# Ethernet_PHY.net
KiCad netlist of a schematic drawn in Altium Designer
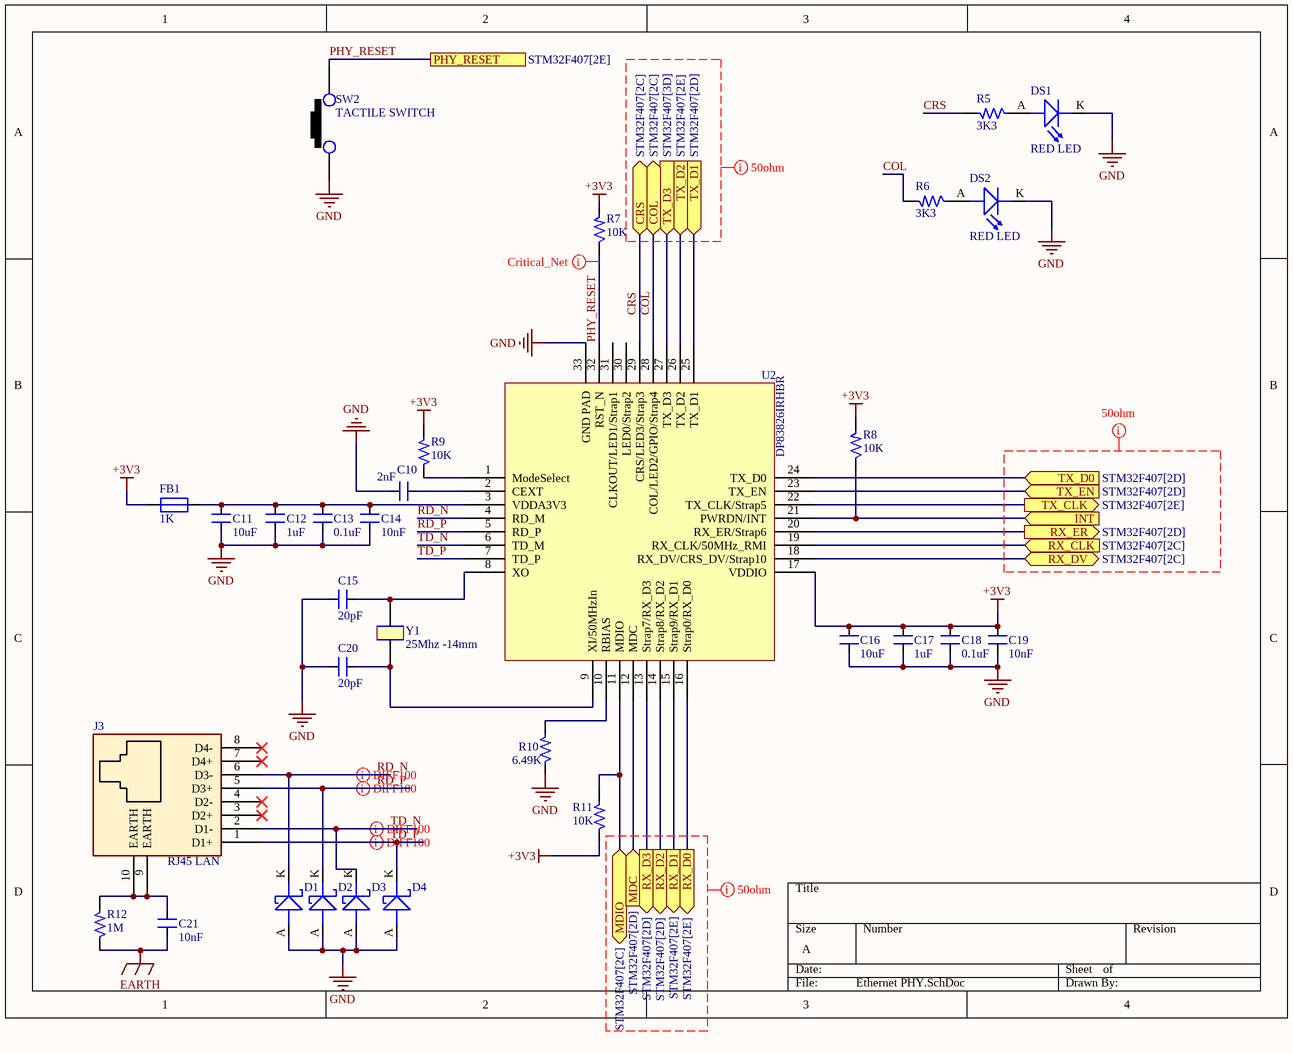
[diagram p0: Ethernet PHY.SchDoc]

(export (version "E")
  (design (tool "Eeschema 10.0.6"))
  (components
    (comp (ref "C10")
      (value "2nF")
      (footprint "CAP_0805")
      (description "2000pF ±10% 50V Ceramic Capacitor X7R 0805 (2012 Metric)")
      (fields
        (field (name "MANUFACTURER") "Samsung Electro-Mechanics")
        (field (name "MANUFACTURER PART NUMBER") "CL21B202KBANNNC")
      )
      (libsource (lib "ESTEEMPCBLIB") (part "CAP_2nF-50V-10%-0805"))
    )
    (comp (ref "C11")
      (value "10uF")
      (footprint "CAP_1206")
      (description "10µF ±10% 50V Ceramic Capacitor X7R 1206 (3216 Metric)")
      (fields
        (field (name "MANUFACTURER") "KEMET")
        (field (name "MANUFACTURER PART NUMBER") "CL31B106KBHNNNE")
      )
      (libsource (lib "ESTEEMPCBLIB") (part "CAP_10uF-50V-10%-1206"))
    )
    (comp (ref "C12")
      (value "1uF")
      (footprint "CAP_0805")
      (description "1µF ±5% 50V Ceramic Capacitor X7R 0805 (2012 Metric)")
      (fields
        (field (name "MANUFACTURER") "Samsung")
        (field (name "MANUFACTURER PART NUMBER") "CC0805JKX7R9BB105")
      )
      (libsource (lib "ESTEEMPCBLIB") (part "CAP_1uF-50V-5%-0805"))
    )
    (comp (ref "C13")
      (value "0.1uF")
      (footprint "CAP_0805")
      (description "0.1µF ±10% 50V Ceramic Capacitor X7R 0805 (2012 Metric)")
      (fields
        (field (name "MANUFACTURER") "Samsung")
        (field (name "MANUFACTURER PART NUMBER") "CL21B104KBCNNNC")
      )
      (libsource (lib "ESTEEMPCBLIB") (part "CAP_0.1uF-50V-10%-0805"))
    )
    (comp (ref "C14")
      (value "10nF")
      (footprint "CAP_0805")
      (description "10000pF ±10% 50V Ceramic Capacitor X7R 0805 (2012 Metric)")
      (fields
        (field (name "MANUFACTURER") "Samsung")
        (field (name "MANUFACTURER PART NUMBER") "C0805C103K5RECAUTO")
      )
      (libsource (lib "ESTEEMPCBLIB") (part "CAP_10nF-50V-10%-0805"))
    )
    (comp (ref "C15")
      (value "20pF")
      (footprint "CAP_0805")
      (description "±10% 50V Ceramic Capacitor C0G, NP0 0805 (2012 Metric)")
      (fields
        (field (name "MANUFACTURER") "AVX Corporation")
        (field (name "MANUFACTURER PART NUMBER") "08055A200KAT2A")
      )
      (libsource (lib "ESTEEMPCBLIB") (part "CAP_20pF-50V-10%-0805"))
    )
    (comp (ref "C16")
      (value "10uF")
      (footprint "CAP_1206")
      (description "10µF ±10% 50V Ceramic Capacitor X7R 1206 (3216 Metric)")
      (fields
        (field (name "MANUFACTURER") "KEMET")
        (field (name "MANUFACTURER PART NUMBER") "CL31B106KBHNNNE")
      )
      (libsource (lib "ESTEEMPCBLIB") (part "CAP_10uF-50V-10%-1206"))
    )
    (comp (ref "C17")
      (value "1uF")
      (footprint "CAP_0805")
      (description "1µF ±5% 50V Ceramic Capacitor X7R 0805 (2012 Metric)")
      (fields
        (field (name "MANUFACTURER") "Samsung")
        (field (name "MANUFACTURER PART NUMBER") "CC0805JKX7R9BB105")
      )
      (libsource (lib "ESTEEMPCBLIB") (part "CAP_1uF-50V-5%-0805"))
    )
    (comp (ref "C18")
      (value "0.1uF")
      (footprint "CAP_0805")
      (description "0.1µF ±10% 50V Ceramic Capacitor X7R 0805 (2012 Metric)")
      (fields
        (field (name "MANUFACTURER") "Samsung")
        (field (name "MANUFACTURER PART NUMBER") "CL21B104KBCNNNC")
      )
      (libsource (lib "ESTEEMPCBLIB") (part "CAP_0.1uF-50V-10%-0805"))
    )
    (comp (ref "C19")
      (value "10nF")
      (footprint "CAP_0805")
      (description "10000pF ±10% 50V Ceramic Capacitor X7R 0805 (2012 Metric)")
      (fields
        (field (name "MANUFACTURER") "Samsung")
        (field (name "MANUFACTURER PART NUMBER") "C0805C103K5RECAUTO")
      )
      (libsource (lib "ESTEEMPCBLIB") (part "CAP_10nF-50V-10%-0805"))
    )
    (comp (ref "C20")
      (value "20pF")
      (footprint "CAP_0805")
      (description "±10% 50V Ceramic Capacitor C0G, NP0 0805 (2012 Metric)")
      (fields
        (field (name "MANUFACTURER") "AVX Corporation")
        (field (name "MANUFACTURER PART NUMBER") "08055A200KAT2A")
      )
      (libsource (lib "ESTEEMPCBLIB") (part "CAP_20pF-50V-10%-0805"))
    )
    (comp (ref "C21")
      (value "10nF")
      (footprint "CAP_P196_102X287_H332_RAD_TH")
      (description "10000pF ±10% 1000V (1kV) Ceramic Capacitor X7R Radial")
      (fields
        (field (name "MANUFACTURER") "Yageo")
        (field (name "MANUFACTURER PART NUMBER") "RDER73A103K2K1H03B")
      )
      (libsource (lib "ESTEEMPCBLIB") (part "CAP_10nF-1KV-10%-RAD-TH"))
    )
    (comp (ref "D1")
      (value "ESD3V3D9-TP")
      (footprint "DIO_SOD-923")
      (description "TVS DIODE 3.3V 8.8V SOD923")
      (fields (field (name "MANUFACTURER") "Micro Commercial Co"))
      (libsource (lib "ESTEEMPCBLIB") (part "DIO-T_3.3V-8.8V-10A-SOD923"))
    )
    (comp (ref "D2")
      (value "ESD3V3D9-TP")
      (footprint "DIO_SOD-923")
      (description "TVS DIODE 3.3V 8.8V SOD923")
      (fields (field (name "MANUFACTURER") "Micro Commercial Co"))
      (libsource (lib "ESTEEMPCBLIB") (part "DIO-T_3.3V-8.8V-10A-SOD923"))
    )
    (comp (ref "D3")
      (value "ESD3V3D9-TP")
      (footprint "DIO_SOD-923")
      (description "TVS DIODE 3.3V 8.8V SOD923")
      (fields (field (name "MANUFACTURER") "Micro Commercial Co"))
      (libsource (lib "ESTEEMPCBLIB") (part "DIO-T_3.3V-8.8V-10A-SOD923"))
    )
    (comp (ref "D4")
      (value "ESD3V3D9-TP")
      (footprint "DIO_SOD-923")
      (description "TVS DIODE 3.3V 8.8V SOD923")
      (fields (field (name "MANUFACTURER") "Micro Commercial Co"))
      (libsource (lib "ESTEEMPCBLIB") (part "DIO-T_3.3V-8.8V-10A-SOD923"))
    )
    (comp (ref "DS1")
      (value "RED LED")
      (footprint "LED_0805")
      (description "Red 631nm LED Indication - Discrete 2V 0805 (2012 Metric)")
      (fields
        (field (name "MANUFACTURER") "Vishay Lite-On")
        (field (name "MANUFACTURER PART NUMBER") "LTST-C171KRKT")
      )
      (libsource (lib "ESTEEMPCBLIB") (part "LED_RED-2V-20mA-0805"))
    )
    (comp (ref "DS2")
      (value "RED LED")
      (footprint "LED_0805")
      (description "Red 631nm LED Indication - Discrete 2V 0805 (2012 Metric)")
      (fields
        (field (name "MANUFACTURER") "Vishay Lite-On")
        (field (name "MANUFACTURER PART NUMBER") "LTST-C171KRKT")
      )
      (libsource (lib "ESTEEMPCBLIB") (part "LED_RED-2V-20mA-0805"))
    )
    (comp (ref "FB1")
      (value "1K")
      (footprint "IND_0805")
      (description "1 kOhms @ 100MHz 1 Power Line Ferrite Bead 0805 (2012 Metric) 1.6A")
      (fields
        (field (name "MANUFACTURER") "Laird")
        (field (name "MANUFACTURER PART NUMBER") "BLM21SP102SH1D")
      )
      (libsource (lib "ESTEEMPCBLIB") (part "FB_1K-100MHZ-1.6A-0805"))
    )
    (comp (ref "J3")
      (value "RJ45 LAN")
      (footprint "CON10_P106_RJ45_TH_ST")
      (description "8 Pins, 2 Row 2.54mm Pitch, right angle Connector, male")
      (fields
        (field (name "MANUFACTURER") "Assmann")
        (field (name "MANUFACTURER PART NUMBER") "A-2004-2-4-LPS-N-R")
      )
      (libsource (lib "ESTEEMPCBLIB") (part "CON-SKT-RJ_8C8P-RA-TH"))
    )
    (comp (ref "R5")
      (value "3K3")
      (footprint "RES_0603")
      (description "3.3 kOhms ±1% 0.1W, 1/10W Chip Resistor 0603 (1608 Metric) Automotive AEC-Q200 Thick Film")
      (fields (field (name "MANUFACTURER") "Wilson") (field (name "MANUFACTURER PART NUMBER") "WR06X3301FTL"))
      (libsource (lib "ESTEEMPCBLIB") (part "RES_3.3K-0.1W-1%-0603"))
    )
    (comp (ref "R6")
      (value "3K3")
      (footprint "RES_0603")
      (description "3.3 kOhms ±1% 0.1W, 1/10W Chip Resistor 0603 (1608 Metric) Automotive AEC-Q200 Thick Film")
      (fields (field (name "MANUFACTURER") "Wilson") (field (name "MANUFACTURER PART NUMBER") "WR06X3301FTL"))
      (libsource (lib "ESTEEMPCBLIB") (part "RES_3.3K-0.1W-1%-0603"))
    )
    (comp (ref "R7")
      (value "10K")
      (footprint "RES_0603")
      (description "10 kOhms ±1% 0.1W, 1/10W Chip Resistor 0603 (1608 Metric) Automotive AEC-Q200 Thick Film")
      (fields (field (name "MANUFACTURER") "Walsin") (field (name "MANUFACTURER PART NUMBER") "WR06X1002FTL"))
      (libsource (lib "ESTEEMPCBLIB") (part "RES_10K-0.1W-1%-0603"))
    )
    (comp (ref "R8")
      (value "10K")
      (footprint "RES_0603")
      (description "10 kOhms ±1% 0.1W, 1/10W Chip Resistor 0603 (1608 Metric) Automotive AEC-Q200 Thick Film")
      (fields (field (name "MANUFACTURER") "Walsin") (field (name "MANUFACTURER PART NUMBER") "WR06X1002FTL"))
      (libsource (lib "ESTEEMPCBLIB") (part "RES_10K-0.1W-1%-0603"))
    )
    (comp (ref "R9")
      (value "10K")
      (footprint "RES_0603")
      (description "10 kOhms ±1% 0.1W, 1/10W Chip Resistor 0603 (1608 Metric) Automotive AEC-Q200 Thick Film")
      (fields (field (name "MANUFACTURER") "Walsin") (field (name "MANUFACTURER PART NUMBER") "WR06X1002FTL"))
      (libsource (lib "ESTEEMPCBLIB") (part "RES_10K-0.1W-1%-0603"))
    )
    (comp (ref "R10")
      (value "6.49K")
      (footprint "RES_0805")
      (description "6.49 kOhms ±1% 0.125W, 1/8W Chip Resistor 0805 (2012 Metric) Moisture Resistant Thick Film")
      (fields
        (field (name "MANUFACTURER") "Stackpole Electronics")
        (field (name "MANUFACTURER PART NUMBER") "RC0805FR-076K49L")
      )
      (libsource (lib "ESTEEMPCBLIB") (part "RES_6.49K-0.125W-1%-0805"))
    )
    (comp (ref "R11")
      (value "10K")
      (footprint "RES_0603")
      (description "10 kOhms ±1% 0.1W, 1/10W Chip Resistor 0603 (1608 Metric) Automotive AEC-Q200 Thick Film")
      (fields (field (name "MANUFACTURER") "Walsin") (field (name "MANUFACTURER PART NUMBER") "WR06X1002FTL"))
      (libsource (lib "ESTEEMPCBLIB") (part "RES_10K-0.1W-1%-0603"))
    )
    (comp (ref "R12")
      (value "1M")
      (footprint "RES_1206")
      (fields (field (name "MANUFACTURER") "Walsin") (field (name "MANUFACTURER PART NUMBER") "WR12X1004FTL"))
      (libsource (lib "ESTEEMPCBLIB") (part "RES_1M-0.25W-1%-1206"))
    )
    (comp (ref "SW2")
      (value "TACTILE SWITCH")
      (footprint "SW_342_SMD")
      (description "Tactile Switch SPST-NO Top Actuated Surface Mount")
      (fields
        (field (name "MANUFACTURER") "ITT C&K")
        (field (name "MANUFACTURER PART NUMBER") "RS-282G05A3-SMRT")
      )
      (libsource (lib "ESTEEMPCBLIB") (part "SW1_RS-282G05A3-SMRT-SMD"))
    )
    (comp (ref "U2")
      (value "DP83826IRHBR")
      (footprint "VQFN32_19_218_23X9_SMD")
      (fields (field (name "MANUFACTURER") "Texas Instruments"))
      (libsource (lib "ESTEEMPCBLIB") (part "IC_DP83826IRHBR"))
    )
    (comp (ref "Y1")
      (value "25Mhz -14mm")
      (footprint "XTAL_314_240X47_SMD")
      (description "25MHz ±30ppm Crystal 20pF 30 Ohms HC-49/US")
      (fields
        (field (name "MANUFACTURER") "Abracon")
        (field (name "MANUFACTURER PART NUMBER") "FOXSDLF/250F-20")
      )
      (libsource (lib "ESTEEMPCBLIB") (part "XTAL_25Mhz-FOXSDLF/250F-20"))
    )
  )
  (nets
    (net (code "1") (name "+3V3") (class "Default")
      (node (ref "C16") (pin "1") (pinfunction "1_1") (pintype "passive"))
      (node (ref "C17") (pin "2") (pinfunction "2_2") (pintype "passive"))
      (node (ref "C18") (pin "2") (pinfunction "2_2") (pintype "passive"))
      (node (ref "C19") (pin "1") (pinfunction "1_1") (pintype "passive"))
      (node (ref "FB1") (pin "1") (pinfunction "1_1") (pintype "passive"))
      (node (ref "R11") (pin "1") (pinfunction "1_1") (pintype "passive"))
      (node (ref "R7") (pin "2") (pinfunction "2_2") (pintype "passive"))
      (node (ref "R8") (pin "2") (pinfunction "2_2") (pintype "passive"))
      (node (ref "R9") (pin "2") (pinfunction "2_2") (pintype "passive"))
      (node (ref "U2") (pin "17") (pinfunction "VDDIO_17") (pintype "passive"))
    )
    (net (code "2") (name "/COL") (class "Default")
      (node (ref "R6") (pin "2") (pinfunction "2_2") (pintype "passive"))
      (node (ref "U2") (pin "28") (pinfunction "COL/LED2/GPIO/Strap4_28") (pintype "passive"))
    )
    (net (code "3") (name "/CRS") (class "Default")
      (node (ref "R5") (pin "2") (pinfunction "2_2") (pintype "passive"))
      (node (ref "U2") (pin "29") (pinfunction "CRS/LED3/Strap3_29") (pintype "passive"))
    )
    (net (code "4") (name "/INT") (class "Default")
      (node (ref "R8") (pin "1") (pinfunction "1_1") (pintype "passive"))
      (node (ref "U2") (pin "21") (pinfunction "PWRDN/INT_21") (pintype "passive"))
    )
    (net (code "5") (name "/MDC") (class "Default")
      (node (ref "U2") (pin "12") (pinfunction "MDC_12") (pintype "passive"))
    )
    (net (code "6") (name "/MDIO") (class "Default")
      (node (ref "R11") (pin "2") (pinfunction "2_2") (pintype "passive"))
      (node (ref "U2") (pin "11") (pinfunction "MDIO_11") (pintype "passive"))
    )
    (net (code "7") (name "/PHY_RESET") (class "Default")
      (node (ref "R7") (pin "1") (pinfunction "1_1") (pintype "passive"))
      (node (ref "SW2") (pin "2") (pinfunction "2_2") (pintype "passive"))
      (node (ref "U2") (pin "32") (pinfunction "RST_N_32") (pintype "passive"))
    )
    (net (code "8") (name "/RD_N") (class "Default")
      (node (ref "D1") (pin "K") (pinfunction "K_K") (pintype "passive"))
      (node (ref "J3") (pin "6") (pinfunction "D3-_6") (pintype "passive"))
      (node (ref "U2") (pin "4") (pinfunction "RD_M_4") (pintype "passive"))
    )
    (net (code "9") (name "/RD_P") (class "Default")
      (node (ref "D2") (pin "K") (pinfunction "K_K") (pintype "passive"))
      (node (ref "J3") (pin "5") (pinfunction "D3+_5") (pintype "passive"))
      (node (ref "U2") (pin "5") (pinfunction "RD_P_5") (pintype "passive"))
    )
    (net (code "10") (name "/RX_CLK") (class "Default")
      (node (ref "U2") (pin "19") (pinfunction "RX_CLK/50MHz_RMI_19") (pintype "passive"))
    )
    (net (code "11") (name "/RX_D0") (class "Default")
      (node (ref "U2") (pin "16") (pinfunction "Strap0/RX_D0_16") (pintype "passive"))
    )
    (net (code "12") (name "/RX_D1") (class "Default")
      (node (ref "U2") (pin "15") (pinfunction "Strap9/RX_D1_15") (pintype "passive"))
    )
    (net (code "13") (name "/RX_D2") (class "Default")
      (node (ref "U2") (pin "14") (pinfunction "Strap8/RX_D2_14") (pintype "passive"))
    )
    (net (code "14") (name "/RX_D3") (class "Default")
      (node (ref "U2") (pin "13") (pinfunction "Strap7/RX_D3_13") (pintype "passive"))
    )
    (net (code "15") (name "/RX_DV") (class "Default")
      (node (ref "U2") (pin "18") (pinfunction "RX_DV/CRS_DV/Strap10_18") (pintype "passive"))
    )
    (net (code "16") (name "/RX_ER") (class "Default")
      (node (ref "U2") (pin "20") (pinfunction "RX_ER/Strap6_20") (pintype "passive"))
    )
    (net (code "17") (name "/TD_N") (class "Default")
      (node (ref "D3") (pin "K") (pinfunction "K_K") (pintype "passive"))
      (node (ref "J3") (pin "2") (pinfunction "D1-_2") (pintype "passive"))
      (node (ref "U2") (pin "6") (pinfunction "TD_M_6") (pintype "passive"))
    )
    (net (code "18") (name "/TD_P") (class "Default")
      (node (ref "D4") (pin "K") (pinfunction "K_K") (pintype "passive"))
      (node (ref "J3") (pin "1") (pinfunction "D1+_1") (pintype "passive"))
      (node (ref "U2") (pin "7") (pinfunction "TD_P_7") (pintype "passive"))
    )
    (net (code "19") (name "/TX_CLK") (class "Default")
      (node (ref "U2") (pin "22") (pinfunction "TX_CLK/Strap5_22") (pintype "passive"))
    )
    (net (code "20") (name "/TX_D0") (class "Default")
      (node (ref "U2") (pin "24") (pinfunction "TX_D0_24") (pintype "passive"))
    )
    (net (code "21") (name "/TX_D1") (class "Default")
      (node (ref "U2") (pin "25") (pinfunction "TX_D1_25") (pintype "passive"))
    )
    (net (code "22") (name "/TX_D2") (class "Default")
      (node (ref "U2") (pin "26") (pinfunction "TX_D2_26") (pintype "passive"))
    )
    (net (code "23") (name "/TX_D3") (class "Default")
      (node (ref "U2") (pin "27") (pinfunction "TX_D3_27") (pintype "passive"))
    )
    (net (code "24") (name "/TX_EN") (class "Default")
      (node (ref "U2") (pin "23") (pinfunction "TX_EN_23") (pintype "passive"))
    )
    (net (code "25") (name "EARTH") (class "Default")
      (node (ref "C21") (pin "2") (pinfunction "2_2") (pintype "passive"))
      (node (ref "R12") (pin "1") (pinfunction "1_1") (pintype "passive"))
    )
    (net (code "26") (name "GND") (class "Default")
      (node (ref "C10") (pin "1") (pinfunction "1_1") (pintype "passive"))
      (node (ref "C11") (pin "2") (pinfunction "2_2") (pintype "passive"))
      (node (ref "C12") (pin "1") (pinfunction "1_1") (pintype "passive"))
      (node (ref "C13") (pin "1") (pinfunction "1_1") (pintype "passive"))
      (node (ref "C14") (pin "2") (pinfunction "2_2") (pintype "passive"))
      (node (ref "C15") (pin "2") (pinfunction "2_2") (pintype "passive"))
      (node (ref "C16") (pin "2") (pinfunction "2_2") (pintype "passive"))
      (node (ref "C17") (pin "1") (pinfunction "1_1") (pintype "passive"))
      (node (ref "C18") (pin "1") (pinfunction "1_1") (pintype "passive"))
      (node (ref "C19") (pin "2") (pinfunction "2_2") (pintype "passive"))
      (node (ref "C20") (pin "2") (pinfunction "2_2") (pintype "passive"))
      (node (ref "D1") (pin "A") (pinfunction "A_A") (pintype "passive"))
      (node (ref "D2") (pin "A") (pinfunction "A_A") (pintype "passive"))
      (node (ref "D3") (pin "A") (pinfunction "A_A") (pintype "passive"))
      (node (ref "D4") (pin "A") (pinfunction "A_A") (pintype "passive"))
      (node (ref "DS1") (pin "K") (pinfunction "CATHODE_K") (pintype "passive"))
      (node (ref "DS2") (pin "K") (pinfunction "CATHODE_K") (pintype "passive"))
      (node (ref "R10") (pin "1") (pinfunction "1_1") (pintype "passive"))
      (node (ref "SW2") (pin "1") (pinfunction "1_1") (pintype "passive"))
      (node (ref "U2") (pin "33") (pinfunction "GND_PAD_33") (pintype "passive"))
    )
    (net (code "27") (name "Net-(C21-Pad1)") (class "Default")
      (node (ref "C21") (pin "1") (pinfunction "1_1") (pintype "passive"))
      (node (ref "J3") (pin "10") (pinfunction "EARTH_10") (pintype "passive"))
      (node (ref "J3") (pin "9") (pinfunction "EARTH_9") (pintype "passive"))
      (node (ref "R12") (pin "2") (pinfunction "2_2") (pintype "passive"))
    )
    (net (code "28") (name "Net-(DS1-ANODE)") (class "Default")
      (node (ref "DS1") (pin "A") (pinfunction "ANODE_A") (pintype "passive"))
      (node (ref "R5") (pin "1") (pinfunction "1_1") (pintype "passive"))
    )
    (net (code "29") (name "Net-(DS2-ANODE)") (class "Default")
      (node (ref "DS2") (pin "A") (pinfunction "ANODE_A") (pintype "passive"))
      (node (ref "R6") (pin "1") (pinfunction "1_1") (pintype "passive"))
    )
    (net (code "30") (name "Net-(U2-CEXT)") (class "Default")
      (node (ref "C10") (pin "2") (pinfunction "2_2") (pintype "passive"))
      (node (ref "U2") (pin "2") (pinfunction "CEXT_2") (pintype "passive"))
    )
    (net (code "31") (name "Net-(U2-ModeSelect)") (class "Default")
      (node (ref "R9") (pin "1") (pinfunction "1_1") (pintype "passive"))
      (node (ref "U2") (pin "1") (pinfunction "ModeSelect_1") (pintype "passive"))
    )
    (net (code "32") (name "Net-(U2-RBIAS)") (class "Default")
      (node (ref "R10") (pin "2") (pinfunction "2_2") (pintype "passive"))
      (node (ref "U2") (pin "10") (pinfunction "RBIAS_10") (pintype "passive"))
    )
    (net (code "33") (name "Net-(U2-VDDA3V3)") (class "Default")
      (node (ref "C11") (pin "1") (pinfunction "1_1") (pintype "passive"))
      (node (ref "C12") (pin "2") (pinfunction "2_2") (pintype "passive"))
      (node (ref "C13") (pin "2") (pinfunction "2_2") (pintype "passive"))
      (node (ref "C14") (pin "1") (pinfunction "1_1") (pintype "passive"))
      (node (ref "FB1") (pin "2") (pinfunction "2_2") (pintype "passive"))
      (node (ref "U2") (pin "3") (pinfunction "VDDA3V3_3") (pintype "passive"))
    )
    (net (code "34") (name "Net-(U2-XI{slash}50MHzIn)") (class "Default")
      (node (ref "C20") (pin "1") (pinfunction "1_1") (pintype "passive"))
      (node (ref "U2") (pin "9") (pinfunction "XI/50MHzIn_9") (pintype "passive"))
      (node (ref "Y1") (pin "1") (pinfunction "1_1") (pintype "passive"))
    )
    (net (code "35") (name "Net-(U2-XO)") (class "Default")
      (node (ref "C15") (pin "1") (pinfunction "1_1") (pintype "passive"))
      (node (ref "U2") (pin "8") (pinfunction "XO_8") (pintype "passive"))
      (node (ref "Y1") (pin "2") (pinfunction "2_2") (pintype "passive"))
    )
    (net (code "36") (name "unconnected-(J3-D2+-Pad3)") (class "Default")
      (node (ref "J3") (pin "3") (pinfunction "D2+_3") (pintype "passive+no_connect"))
    )
    (net (code "37") (name "unconnected-(J3-D2--Pad4)") (class "Default")
      (node (ref "J3") (pin "4") (pinfunction "D2-_4") (pintype "passive+no_connect"))
    )
    (net (code "38") (name "unconnected-(J3-D4+-Pad7)") (class "Default")
      (node (ref "J3") (pin "7") (pinfunction "D4+_7") (pintype "passive+no_connect"))
    )
    (net (code "39") (name "unconnected-(J3-D4--Pad8)") (class "Default")
      (node (ref "J3") (pin "8") (pinfunction "D4-_8") (pintype "passive+no_connect"))
    )
    (net (code "40") (name "unconnected-(U2-CLKOUT{slash}LED1{slash}Strap1-Pad31)") (class "Default")
      (node (ref "U2") (pin "31") (pinfunction "CLKOUT/LED1/Strap1_31") (pintype "passive"))
    )
    (net (code "41") (name "unconnected-(U2-LED0{slash}Strap2-Pad30)") (class "Default")
      (node (ref "U2") (pin "30") (pinfunction "LED0/Strap2_30") (pintype "passive"))
    )
  )
)
